# SCH_d_01_e_04.net
KiCad netlist of a schematic drawn in EasyEDA
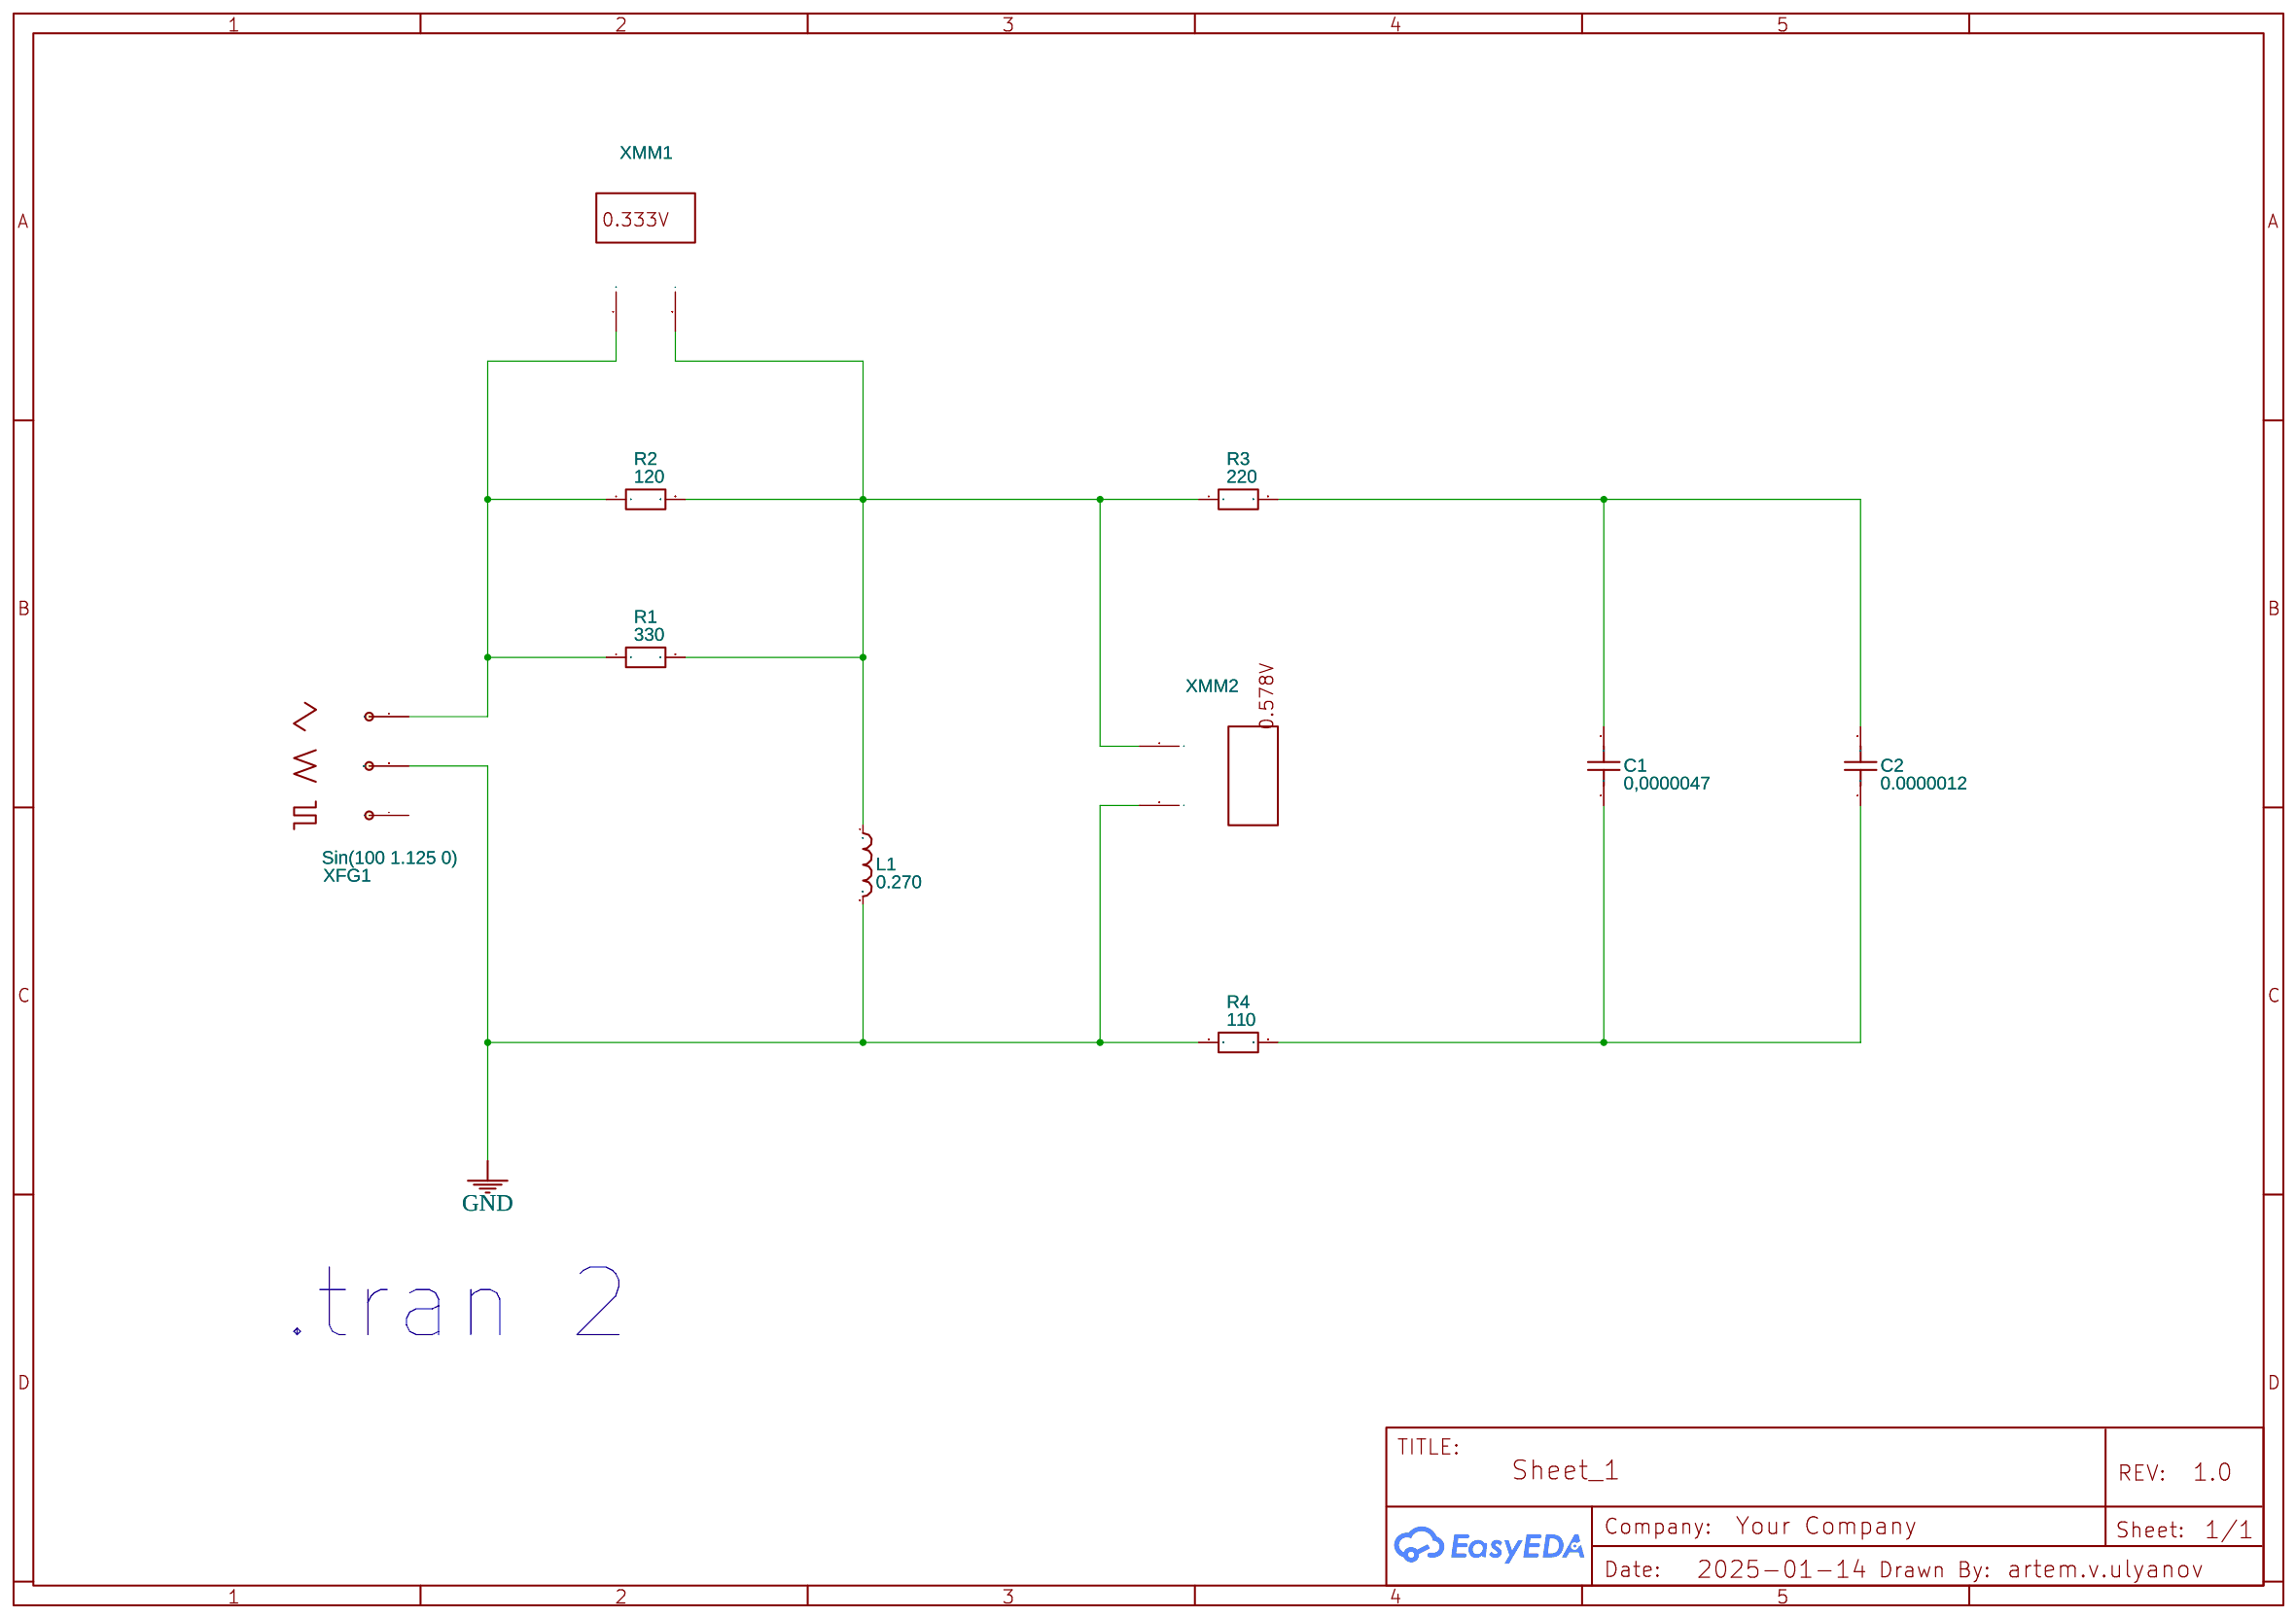
[diagram p0: schematic sheet]

(export (version "E")
  (design (tool "Eeschema 10.0.6"))
  (components
    (comp (ref "C1") (value "0,0000047") (libsource (lib "") (part "Capacitor_US")))
    (comp (ref "C2") (value "0.0000012") (libsource (lib "") (part "Capacitor_US")))
    (comp (ref "L1") (value "0.270") (libsource (lib "") (part "Inductor")))
    (comp (ref "R1") (value "330") (libsource (lib "") (part "R_0603_EU")))
    (comp (ref "R2") (value "120") (libsource (lib "") (part "R_0603_EU")))
    (comp (ref "R3") (value "220") (libsource (lib "") (part "R_0603_EU")))
    (comp (ref "R4") (value "110") (libsource (lib "") (part "R_0603_EU")))
    (comp (ref "XFG1") (value "Sin(100 1.125 0)") (libsource (lib "") (part "FUNCTIONGENERATOR")))
    (comp (ref "XMM1") (value "Multimeter") (libsource (lib "") (part "MULTIMETER_1")))
    (comp (ref "XMM2") (value "Multimeter") (libsource (lib "") (part "MULTIMETER")))
  )
  (nets
    (net (code "1") (name "GND") (class "Default")
      (node (ref "L1") (pin "2") (pinfunction "2_2") (pintype "unspecified"))
      (node (ref "R4") (pin "1") (pinfunction "1_1") (pintype "unspecified"))
      (node (ref "XFG1") (pin "COM") (pinfunction "COM_COM") (pintype "unspecified"))
      (node (ref "XMM2") (pin "2") (pinfunction "I_2") (pintype "unspecified"))
    )
    (net (code "2") (name "Net-(C1-Pad1)") (class "Default")
      (node (ref "C1") (pin "1") (pinfunction "1_1") (pintype "unspecified"))
      (node (ref "C2") (pin "1") (pinfunction "1_1") (pintype "unspecified"))
      (node (ref "R4") (pin "2") (pinfunction "2_2") (pintype "unspecified"))
    )
    (net (code "3") (name "Net-(C1-Pad2)") (class "Default")
      (node (ref "C1") (pin "2") (pinfunction "2_2") (pintype "unspecified"))
      (node (ref "C2") (pin "2") (pinfunction "2_2") (pintype "unspecified"))
      (node (ref "R3") (pin "2") (pinfunction "2_2") (pintype "unspecified"))
    )
    (net (code "4") (name "Net-(XMM1-+)") (class "Default")
      (node (ref "R1") (pin "1") (pinfunction "1_1") (pintype "unspecified"))
      (node (ref "R2") (pin "1") (pinfunction "1_1") (pintype "unspecified"))
      (node (ref "XFG1") (pin "+") (pinfunction "+_+") (pintype "unspecified"))
      (node (ref "XMM1") (pin "1") (pinfunction "+_1") (pintype "unspecified"))
    )
    (net (code "5") (name "Net-(XMM1-I)") (class "Default")
      (node (ref "L1") (pin "1") (pinfunction "1_1") (pintype "unspecified"))
      (node (ref "R1") (pin "2") (pinfunction "2_2") (pintype "unspecified"))
      (node (ref "R2") (pin "2") (pinfunction "2_2") (pintype "unspecified"))
      (node (ref "R3") (pin "1") (pinfunction "1_1") (pintype "unspecified"))
      (node (ref "XMM1") (pin "2") (pinfunction "I_2") (pintype "unspecified"))
      (node (ref "XMM2") (pin "1") (pinfunction "+_1") (pintype "unspecified"))
    )
    (net (code "6") (name "unconnected-(XFG1-Pad-)") (class "Default")
      (node (ref "XFG1") (pin "-") (pinfunction "-_-") (pintype "unspecified"))
    )
  )
)
